# pcb.net
KiCad netlist of a schematic drawn in Altium Designer
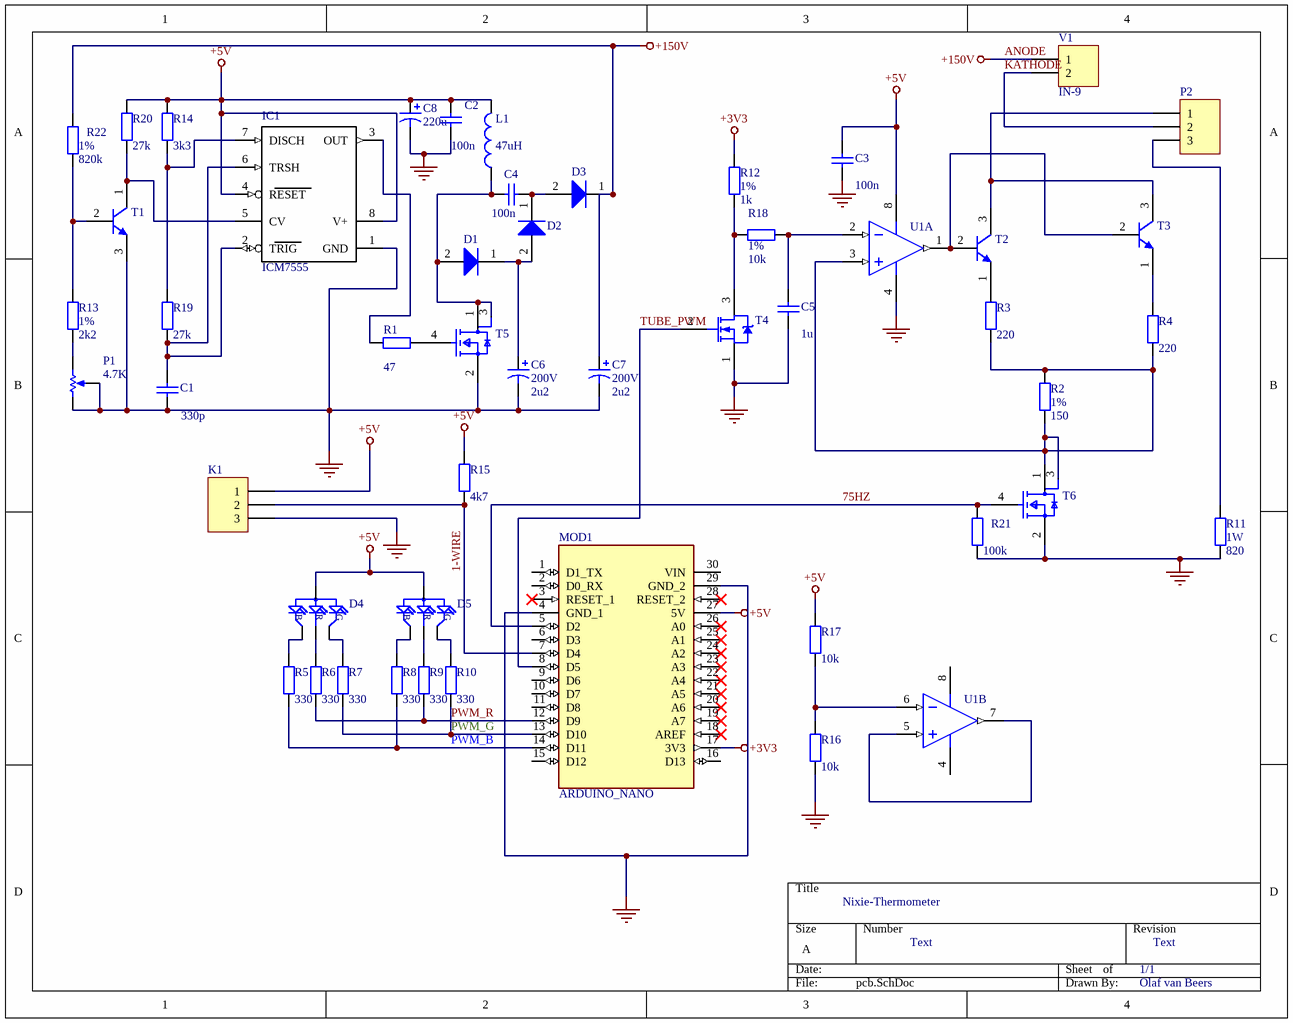
[diagram p0: pcb.SchDoc]

(export (version "E")
  (design (tool "Eeschema 10.0.6"))
  (components
    (comp (ref "C1")
      (value "330p")
      (footprint "RAD-0.3")
      (description "Capacitor")
      (fields (field (name "Comment") "Cap") (field (name "PUBLISHER") "Altium Limited"))
      (libsource (lib "Miscellaneous Devices") (part "Cap"))
    )
    (comp (ref "C2")
      (value "100n")
      (footprint "RAD-0.3")
      (description "Capacitor")
      (fields (field (name "Comment") "Cap") (field (name "PUBLISHER") "Altium Limited"))
      (libsource (lib "Miscellaneous Devices") (part "Cap"))
    )
    (comp (ref "C3")
      (value "100n")
      (footprint "RAD-0.3")
      (description "Capacitor")
      (fields (field (name "Comment") "Cap") (field (name "PUBLISHER") "Altium Limited"))
      (libsource (lib "Miscellaneous Devices") (part "Cap"))
    )
    (comp (ref "C4")
      (value "100n")
      (footprint "RAD-0.3")
      (description "Capacitor")
      (fields (field (name "Comment") "Cap") (field (name "PUBLISHER") "Altium Limited"))
      (libsource (lib "Miscellaneous Devices") (part "Cap"))
    )
    (comp (ref "C5")
      (value "1u")
      (footprint "RAD-0.3")
      (description "Capacitor")
      (fields (field (name "Comment") "Cap") (field (name "PUBLISHER") "Altium Limited"))
      (libsource (lib "Miscellaneous Devices") (part "Cap"))
    )
    (comp (ref "C6")
      (value "200V")
      (footprint "Miscellaneous Devices:RB7.6-15")
      (description "Polarized Capacitor (Radial)")
      (fields (field (name "ALTIUM_VALUE") "2u2") (field (name "PUBLISHER") "Altium Limited"))
      (libsource (lib "Miscellaneous Devices") (part "Cap Pol1"))
    )
    (comp (ref "C7")
      (value "200V")
      (footprint "RB7.6-15")
      (description "Polarized Capacitor (Radial)")
      (fields (field (name "ALTIUM_VALUE") "2u2") (field (name "PUBLISHER") "Altium Limited"))
      (libsource (lib "Miscellaneous Devices") (part "Cap Pol1"))
    )
    (comp (ref "C8")
      (value "220u")
      (footprint "RB7.6-15")
      (description "Polarized Capacitor (Radial)")
      (fields (field (name "Comment") "Cap Pol1") (field (name "PUBLISHER") "Altium Limited"))
      (libsource (lib "Miscellaneous Devices") (part "Cap Pol1"))
    )
    (comp (ref "D1")
      (value "MUR160G")
      (footprint "ONSC-AXIAL_LEAD-2-59-10_P")
      (description "SWITCHMODE(TM) Power Rectifier, 2-Pin Axial_Lead, Pb-Free, Bulk Bag")
      (fields (field (name "MANUFACTURER") "On Semiconductor"))
      (libsource (lib "Components - 04.03.20 - 18.02") (part "CMP-0902-00129-1"))
    )
    (comp (ref "D2")
      (value "MUR160G")
      (footprint "ONSC-AXIAL_LEAD-2-59-10_P")
      (description "SWITCHMODE(TM) Power Rectifier, 2-Pin Axial_Lead, Pb-Free, Bulk Bag")
      (fields (field (name "MANUFACTURER") "On Semiconductor"))
      (libsource (lib "Components - 04.03.20 - 18.02") (part "CMP-0902-00129-1"))
    )
    (comp (ref "D3")
      (value "MUR160G")
      (footprint "ONSC-AXIAL_LEAD-2-59-10_P")
      (description "SWITCHMODE(TM) Power Rectifier, 2-Pin Axial_Lead, Pb-Free, Bulk Bag")
      (fields (field (name "MANUFACTURER") "On Semiconductor"))
      (libsource (lib "Components - 04.03.20 - 18.02") (part "CMP-0902-00129-1"))
    )
    (comp (ref "D4")
      (value "DIP-LED-RGB-COMMON-ANODE(4P-D8MM)")
      (footprint "*LED4-2.0-D8.0MM")
      (description "DIP LED RGB Common Anode")
      (fields (field (name "MF") "Chengguangxing") (field (name "MP") "CZXR-80RGB03-A"))
      (libsource (lib "DIP-LED-RGB-COMMON-ANODE_4P-D8MM_") (part "DIP-LED-RGB-COMMON-ANODE(4P-D8MM)"))
    )
    (comp (ref "D5")
      (value "DIP-LED-RGB-COMMON-ANODE(4P-D8MM)")
      (footprint "*LED4-2.0-D8.0MM")
      (description "DIP LED RGB Common Anode")
      (fields (field (name "MF") "Chengguangxing") (field (name "MP") "CZXR-80RGB03-A"))
      (libsource (lib "DIP-LED-RGB-COMMON-ANODE_4P-D8MM_") (part "DIP-LED-RGB-COMMON-ANODE(4P-D8MM)"))
    )
    (comp (ref "IC1") (value "ICM7555") (footprint "*DIL08") (libsource (lib "ICM7555") (part "ICM7555")))
    (comp (ref "K1")
      (value "Header 3")
      (footprint "HDR1X3")
      (description "Header, 3-Pin")
      (fields (field (name "PUBLISHER") "Altium Limited"))
      (libsource (lib "Miscellaneous Connectors") (part "Header 3"))
    )
    (comp (ref "L1")
      (value "47uH")
      (footprint "INDC3216")
      (description "Inductor")
      (fields (field (name "PUBLISHER") "Altium Limited"))
      (libsource (lib "Miscellaneous Devices") (part "Inductor"))
    )
    (comp (ref "MOD1")
      (value "ARDUINO_NANO")
      (footprint "ARDUINO_A000005")
      (description "ATmega328 Arduino Nano AVRÂ® ATmega AVR MCU 8-Bit Embedded Evaluation Board")
      (fields (field (name "MP") "A000005") (field (name "DIGI-KEY_PART_NUMBER") "1050-1001-ND"))
      (libsource (lib "A000005") (part "A000005"))
    )
    (comp (ref "P1")
      (value "4.7K")
      (footprint "VR4")
      (description "Potentiometer")
      (fields (field (name "Comment") "RPot") (field (name "PUBLISHER") "Altium Limited"))
      (libsource (lib "Miscellaneous Devices") (part "RPot"))
    )
    (comp (ref "P2")
      (value "Header 3")
      (footprint "HDR1X3")
      (description "Header, 3-Pin")
      (fields (field (name "PUBLISHER") "Altium Limited"))
      (libsource (lib "") (part "Header 3_1"))
    )
    (comp (ref "R1")
      (value "47")
      (footprint "Miscellaneous Devices:AXIAL-0.4")
      (description "Resistor")
      (fields (field (name "Comment") "Res2") (field (name "PUBLISHER") "Altium Limited"))
      (libsource (lib "") (part "Res2_2"))
    )
    (comp (ref "R2")
      (value "1%")
      (footprint "AXIAL-0.4")
      (description "Resistor")
      (fields (field (name "ALTIUM_VALUE") "150") (field (name "PUBLISHER") "Altium Limited"))
      (libsource (lib "") (part "Res2_1"))
    )
    (comp (ref "R3")
      (value "220")
      (footprint "Miscellaneous Devices:AXIAL-0.4")
      (description "Resistor")
      (fields (field (name "Comment") "Res2") (field (name "PUBLISHER") "Altium Limited"))
      (libsource (lib "") (part "Res2_1"))
    )
    (comp (ref "R4")
      (value "220")
      (footprint "Miscellaneous Devices:AXIAL-0.4")
      (description "Resistor")
      (fields (field (name "Comment") "Res2") (field (name "PUBLISHER") "Altium Limited"))
      (libsource (lib "") (part "Res2_1"))
    )
    (comp (ref "R5")
      (value "330")
      (footprint "Miscellaneous Devices:AXIAL-0.4")
      (description "Resistor")
      (fields (field (name "Comment") "Res2") (field (name "PUBLISHER") "Altium Limited"))
      (libsource (lib "") (part "Res2_1"))
    )
    (comp (ref "R6")
      (value "330")
      (footprint "Miscellaneous Devices:AXIAL-0.4")
      (description "Resistor")
      (fields (field (name "Comment") "Res2") (field (name "PUBLISHER") "Altium Limited"))
      (libsource (lib "") (part "Res2_1"))
    )
    (comp (ref "R7")
      (value "330")
      (footprint "Miscellaneous Devices:AXIAL-0.4")
      (description "Resistor")
      (fields (field (name "Comment") "Res2") (field (name "PUBLISHER") "Altium Limited"))
      (libsource (lib "") (part "Res2_1"))
    )
    (comp (ref "R8")
      (value "330")
      (footprint "Miscellaneous Devices:AXIAL-0.4")
      (description "Resistor")
      (fields (field (name "Comment") "Res2") (field (name "PUBLISHER") "Altium Limited"))
      (libsource (lib "") (part "Res2_1"))
    )
    (comp (ref "R9")
      (value "330")
      (footprint "Miscellaneous Devices:AXIAL-0.4")
      (description "Resistor")
      (fields (field (name "Comment") "Res2") (field (name "PUBLISHER") "Altium Limited"))
      (libsource (lib "") (part "Res2_1"))
    )
    (comp (ref "R10")
      (value "330")
      (footprint "Miscellaneous Devices:AXIAL-0.4")
      (description "Resistor")
      (fields (field (name "Comment") "Res2") (field (name "PUBLISHER") "Altium Limited"))
      (libsource (lib "") (part "Res2_1"))
    )
    (comp (ref "R11")
      (value "1W")
      (footprint "AXIAL-0.4")
      (description "Resistor")
      (fields (field (name "ALTIUM_VALUE") "820") (field (name "PUBLISHER") "Altium Limited"))
      (libsource (lib "Miscellaneous Devices") (part "Res2"))
    )
    (comp (ref "R12")
      (value "1%")
      (footprint "AXIAL-0.4")
      (description "Resistor")
      (fields (field (name "ALTIUM_VALUE") "1k") (field (name "PUBLISHER") "Altium Limited"))
      (libsource (lib "") (part "Res2_1"))
    )
    (comp (ref "R13")
      (value "1%")
      (footprint "AXIAL-0.4")
      (description "Resistor")
      (fields (field (name "ALTIUM_VALUE") "2k2") (field (name "PUBLISHER") "Altium Limited"))
      (libsource (lib "") (part "Res2_1"))
    )
    (comp (ref "R14")
      (value "3k3")
      (footprint "Miscellaneous Devices:AXIAL-0.4")
      (description "Resistor")
      (fields (field (name "Comment") "Res2") (field (name "PUBLISHER") "Altium Limited"))
      (libsource (lib "") (part "Res2_1"))
    )
    (comp (ref "R15")
      (value "4k7")
      (footprint "Miscellaneous Devices:AXIAL-0.4")
      (description "Resistor")
      (fields (field (name "Comment") "Res2") (field (name "PUBLISHER") "Altium Limited"))
      (libsource (lib "") (part "Res2_1"))
    )
    (comp (ref "R16")
      (value "10k")
      (footprint "Miscellaneous Devices:AXIAL-0.4")
      (description "Resistor")
      (fields (field (name "Comment") "Res2") (field (name "PUBLISHER") "Altium Limited"))
      (libsource (lib "") (part "Res2_1"))
    )
    (comp (ref "R17")
      (value "10k")
      (footprint "Miscellaneous Devices:AXIAL-0.4")
      (description "Resistor")
      (fields (field (name "Comment") "Res2") (field (name "PUBLISHER") "Altium Limited"))
      (libsource (lib "") (part "Res2_1"))
    )
    (comp (ref "R18")
      (value "1%")
      (footprint "AXIAL-0.4")
      (description "Resistor")
      (fields (field (name "ALTIUM_VALUE") "10k") (field (name "PUBLISHER") "Altium Limited"))
      (libsource (lib "") (part "Res2_2"))
    )
    (comp (ref "R19")
      (value "27k")
      (footprint "Miscellaneous Devices:AXIAL-0.4")
      (description "Resistor")
      (fields (field (name "Comment") "Res2") (field (name "PUBLISHER") "Altium Limited"))
      (libsource (lib "") (part "Res2_1"))
    )
    (comp (ref "R20")
      (value "27k")
      (footprint "Miscellaneous Devices:AXIAL-0.4")
      (description "Resistor")
      (fields (field (name "Comment") "Res2") (field (name "PUBLISHER") "Altium Limited"))
      (libsource (lib "") (part "Res2_1"))
    )
    (comp (ref "R21")
      (value "100k")
      (footprint "Miscellaneous Devices:AXIAL-0.4")
      (description "Resistor")
      (fields (field (name "Comment") "Res2") (field (name "PUBLISHER") "Altium Limited"))
      (libsource (lib "") (part "Res2_1"))
    )
    (comp (ref "R22")
      (value "1%")
      (footprint "AXIAL-0.4")
      (description "Resistor")
      (fields (field (name "ALTIUM_VALUE") "820k") (field (name "PUBLISHER") "Altium Limited"))
      (libsource (lib "") (part "Res2_1"))
    )
    (comp (ref "T1")
      (value "BC547B")
      (footprint "ONSC-TO-92-3-29-11")
      (description "Amplifier Transistor, NPN Silicon, 3-Pin TO-92, Bulk Box")
      (fields (field (name "MANUFACTURER") "On Semiconductor"))
      (libsource (lib "Components - 04.03.20 - 18.02") (part "CMP-1048-01467-1"))
    )
    (comp (ref "T2")
      (value "MPSA42")
      (footprint "ONSC-TO-92-3-29-11")
      (description "High Voltage Transistor, NPN Silicon, 3-Pin TO-92, Bulk Box")
      (fields (field (name "MANUFACTURER") "On Semiconductor"))
      (libsource (lib "Components - 04.03.20 - 18.02") (part "CMP-1048-01390-1"))
    )
    (comp (ref "T3")
      (value "MPSA42")
      (footprint "ONSC-TO-92-3-29-11")
      (description "High Voltage Transistor, NPN Silicon, 3-Pin TO-92, Bulk Box")
      (fields (field (name "MANUFACTURER") "On Semiconductor"))
      (libsource (lib "Components - 04.03.20 - 18.02") (part "CMP-1048-01390-1"))
    )
    (comp (ref "T4")
      (value "2N7000")
      (footprint "ONSC-TO-92-3-29-11")
      (description "Small Signal MOSFET, 200 mA, 60 V, N-Channel, 3-Pin TO-92, Bulk Box")
      (fields (field (name "MANUFACTURER") "On Semiconductor"))
      (libsource (lib "Components - 04.03.20 - 18.02") (part "CMP-1058-00936-1"))
    )
    (comp (ref "T5")
      (value "IRFD110PBF")
      (footprint "Vishay_X10-0386_MFG")
      (libsource (lib "Trans_Vishay_IRFD110PBF_eec") (part "IRFD110PBF"))
    )
    (comp (ref "T6")
      (value "IRFD110PBF")
      (footprint "Vishay_X10-0386_MFG")
      (libsource (lib "Trans_Vishay_IRFD110PBF_eec") (part "IRFD110PBF"))
    )
    (comp (ref "U1")
      (value "LM6142AIM")
      (footprint "D0008A_N")
      (description "Dual High Speed/Low Power 17 MHz Rail-to-Rail I/O Operational Amplifier, 8-pin Narrow SOIC")
      (fields (field (name "MANUFACTURER") "Texas Instruments"))
      (libsource (lib "Altium Content Vault") (part "AMP-OPA-LM6132-8"))
    )
    (comp (ref "V1")
      (value "IN-9")
      (footprint "HDR1X2")
      (description "Header, 2-Pin")
      (fields (field (name "PUBLISHER") "Altium Limited"))
      (libsource (lib "Miscellaneous Connectors") (part "Header 2"))
    )
  )
  (nets
    (net (code "1") (name "+3V3") (class "Default")
      (node (ref "MOD1") (pin "17") (pinfunction "3V3_17") (pintype "output"))
      (node (ref "R12") (pin "2") (pinfunction "2_2") (pintype "passive"))
    )
    (net (code "2") (name "+5V") (class "Default")
      (node (ref "C2") (pin "2") (pinfunction "2_2") (pintype "passive"))
      (node (ref "C3") (pin "2") (pinfunction "2_2") (pintype "passive"))
      (node (ref "C8") (pin "1") (pinfunction "1_1") (pintype "passive"))
      (node (ref "D4") (pin "2") (pinfunction "POS_2") (pintype "bidirectional"))
      (node (ref "D5") (pin "2") (pinfunction "POS_2") (pintype "bidirectional"))
      (node (ref "IC1") (pin "4") (pinfunction "RESET_4") (pintype "input"))
      (node (ref "IC1") (pin "8") (pinfunction "V+_8") (pintype "power_in"))
      (node (ref "K1") (pin "1") (pinfunction "1_1") (pintype "passive"))
      (node (ref "L1") (pin "2") (pinfunction "2_2") (pintype "passive"))
      (node (ref "MOD1") (pin "27") (pinfunction "5V_27") (pintype "power_in"))
      (node (ref "R14") (pin "2") (pinfunction "2_2") (pintype "passive"))
      (node (ref "R15") (pin "2") (pinfunction "2_2") (pintype "passive"))
      (node (ref "R17") (pin "2") (pinfunction "2_2") (pintype "passive"))
      (node (ref "R20") (pin "2") (pinfunction "2_2") (pintype "passive"))
      (node (ref "U1") (pin "8") (pinfunction "V+_8") (pintype "power_in"))
    )
    (net (code "3") (name "+150V") (class "Default")
      (node (ref "C7") (pin "1") (pinfunction "1_1") (pintype "passive"))
      (node (ref "D3") (pin "1") (pinfunction "K_1") (pintype "passive"))
      (node (ref "R22") (pin "2") (pinfunction "2_2") (pintype "passive"))
      (node (ref "V1") (pin "1") (pinfunction "1_1") (pintype "passive"))
    )
    (net (code "4") (name "/1-WIRE") (class "Default")
      (node (ref "K1") (pin "2") (pinfunction "2_2") (pintype "passive"))
      (node (ref "MOD1") (pin "7") (pinfunction "D4_7") (pintype "bidirectional"))
      (node (ref "R15") (pin "1") (pinfunction "1_1") (pintype "passive"))
    )
    (net (code "5") (name "/75HZ") (class "Default")
      (node (ref "MOD1") (pin "5") (pinfunction "D2_5") (pintype "bidirectional"))
      (node (ref "R21") (pin "2") (pinfunction "2_2") (pintype "passive"))
      (node (ref "T6") (pin "4") (pinfunction "G_4") (pintype "passive"))
    )
    (net (code "6") (name "/KATHODE") (class "Default")
      (node (ref "P2") (pin "2") (pinfunction "2_2") (pintype "passive"))
      (node (ref "V1") (pin "2") (pinfunction "2_2") (pintype "passive"))
    )
    (net (code "7") (name "/PWM_B") (class "Default")
      (node (ref "MOD1") (pin "14") (pinfunction "D11_14") (pintype "bidirectional"))
      (node (ref "R5") (pin "1") (pinfunction "1_1") (pintype "passive"))
      (node (ref "R8") (pin "1") (pinfunction "1_1") (pintype "passive"))
    )
    (net (code "8") (name "/PWM_G") (class "Default")
      (node (ref "MOD1") (pin "12") (pinfunction "D9_12") (pintype "bidirectional"))
      (node (ref "MOD1") (pin "13") (pinfunction "D10_13") (pintype "bidirectional"))
      (node (ref "R10") (pin "1") (pinfunction "1_1") (pintype "passive"))
      (node (ref "R6") (pin "1") (pinfunction "1_1") (pintype "passive"))
      (node (ref "R7") (pin "1") (pinfunction "1_1") (pintype "passive"))
      (node (ref "R9") (pin "1") (pinfunction "1_1") (pintype "passive"))
    )
    (net (code "9") (name "/TUBE_PWM") (class "Default")
      (node (ref "MOD1") (pin "8") (pinfunction "D5_8") (pintype "bidirectional"))
      (node (ref "T4") (pin "2") (pinfunction "G_2") (pintype "passive"))
    )
    (net (code "10") (name "GND") (class "Default")
      (node (ref "C1") (pin "1") (pinfunction "1_1") (pintype "passive"))
      (node (ref "C2") (pin "1") (pinfunction "1_1") (pintype "passive"))
      (node (ref "C3") (pin "1") (pinfunction "1_1") (pintype "passive"))
      (node (ref "C5") (pin "1") (pinfunction "1_1") (pintype "passive"))
      (node (ref "C6") (pin "2") (pinfunction "2_2") (pintype "passive"))
      (node (ref "C7") (pin "2") (pinfunction "2_2") (pintype "passive"))
      (node (ref "C8") (pin "2") (pinfunction "2_2") (pintype "passive"))
      (node (ref "IC1") (pin "1") (pinfunction "GND_1") (pintype "power_in"))
      (node (ref "K1") (pin "3") (pinfunction "3_3") (pintype "passive"))
      (node (ref "MOD1") (pin "29") (pinfunction "GND_2_29") (pintype "power_in"))
      (node (ref "MOD1") (pin "4") (pinfunction "GND_1_4") (pintype "power_in"))
      (node (ref "P1") (pin "1") (pinfunction "TOP_1") (pintype "passive"))
      (node (ref "P1") (pin "3") (pinfunction "TAP_3") (pintype "passive"))
      (node (ref "R11") (pin "2") (pinfunction "2_2") (pintype "passive"))
      (node (ref "R16") (pin "1") (pinfunction "1_1") (pintype "passive"))
      (node (ref "R21") (pin "1") (pinfunction "1_1") (pintype "passive"))
      (node (ref "T1") (pin "3") (pinfunction "E_3") (pintype "passive"))
      (node (ref "T4") (pin "1") (pinfunction "S_1") (pintype "passive"))
      (node (ref "T5") (pin "2") (pinfunction "S_2") (pintype "passive"))
      (node (ref "T6") (pin "2") (pinfunction "S_2") (pintype "passive"))
      (node (ref "U1") (pin "4") (pinfunction "V-_4") (pintype "power_in"))
    )
    (net (code "11") (name "Net-(D1-A)") (class "Default")
      (node (ref "C4") (pin "1") (pinfunction "1_1") (pintype "passive"))
      (node (ref "D1") (pin "2") (pinfunction "A_2") (pintype "passive"))
      (node (ref "L1") (pin "1") (pinfunction "1_1") (pintype "passive"))
      (node (ref "T5") (pin "1") (pinfunction "D_1") (pintype "passive"))
      (node (ref "T5") (pin "3") (pinfunction "D_3") (pintype "passive"))
    )
    (net (code "12") (name "Net-(D1-K)") (class "Default")
      (node (ref "C6") (pin "1") (pinfunction "1_1") (pintype "passive"))
      (node (ref "D1") (pin "1") (pinfunction "K_1") (pintype "passive"))
      (node (ref "D2") (pin "2") (pinfunction "A_2") (pintype "passive"))
    )
    (net (code "13") (name "Net-(D2-K)") (class "Default")
      (node (ref "C4") (pin "2") (pinfunction "2_2") (pintype "passive"))
      (node (ref "D2") (pin "1") (pinfunction "K_1") (pintype "passive"))
      (node (ref "D3") (pin "2") (pinfunction "A_2") (pintype "passive"))
    )
    (net (code "14") (name "Net-(D4-B)") (class "Default")
      (node (ref "D4") (pin "4") (pinfunction "B_4") (pintype "bidirectional"))
      (node (ref "R5") (pin "2") (pinfunction "2_2") (pintype "passive"))
    )
    (net (code "15") (name "Net-(D4-G)") (class "Default")
      (node (ref "D4") (pin "3") (pinfunction "G_3") (pintype "bidirectional"))
      (node (ref "R7") (pin "2") (pinfunction "2_2") (pintype "passive"))
    )
    (net (code "16") (name "Net-(D4-R)") (class "Default")
      (node (ref "D4") (pin "1") (pinfunction "R_1") (pintype "bidirectional"))
      (node (ref "R6") (pin "2") (pinfunction "2_2") (pintype "passive"))
    )
    (net (code "17") (name "Net-(D5-B)") (class "Default")
      (node (ref "D5") (pin "4") (pinfunction "B_4") (pintype "bidirectional"))
      (node (ref "R8") (pin "2") (pinfunction "2_2") (pintype "passive"))
    )
    (net (code "18") (name "Net-(D5-G)") (class "Default")
      (node (ref "D5") (pin "3") (pinfunction "G_3") (pintype "bidirectional"))
      (node (ref "R10") (pin "2") (pinfunction "2_2") (pintype "passive"))
    )
    (net (code "19") (name "Net-(D5-R)") (class "Default")
      (node (ref "D5") (pin "1") (pinfunction "R_1") (pintype "bidirectional"))
      (node (ref "R9") (pin "2") (pinfunction "2_2") (pintype "passive"))
    )
    (net (code "20") (name "Net-(IC1-CV)") (class "Default")
      (node (ref "IC1") (pin "5") (pinfunction "CV_5") (pintype "passive"))
      (node (ref "R20") (pin "1") (pinfunction "1_1") (pintype "passive"))
      (node (ref "T1") (pin "1") (pinfunction "C_1") (pintype "passive"))
    )
    (net (code "21") (name "Net-(IC1-DISCH)") (class "Default")
      (node (ref "IC1") (pin "7") (pinfunction "DISCH_7") (pintype "input"))
      (node (ref "R14") (pin "1") (pinfunction "1_1") (pintype "passive"))
      (node (ref "R19") (pin "2") (pinfunction "2_2") (pintype "passive"))
    )
    (net (code "22") (name "Net-(IC1-OUT)") (class "Default")
      (node (ref "IC1") (pin "3") (pinfunction "OUT_3") (pintype "output"))
      (node (ref "R1") (pin "1") (pinfunction "1_1") (pintype "passive"))
    )
    (net (code "23") (name "Net-(IC1-TRIG)") (class "Default")
      (node (ref "C1") (pin "2") (pinfunction "2_2") (pintype "passive"))
      (node (ref "IC1") (pin "2") (pinfunction "TRIG_2") (pintype "bidirectional"))
      (node (ref "IC1") (pin "6") (pinfunction "TRSH_6") (pintype "input"))
      (node (ref "R19") (pin "1") (pinfunction "1_1") (pintype "passive"))
    )
    (net (code "24") (name "Net-(P1-BOT)") (class "Default")
      (node (ref "P1") (pin "2") (pinfunction "BOT_2") (pintype "passive"))
      (node (ref "R13") (pin "1") (pinfunction "1_1") (pintype "passive"))
    )
    (net (code "25") (name "Net-(P2-Pad3)") (class "Default")
      (node (ref "P2") (pin "3") (pinfunction "3_3") (pintype "passive"))
      (node (ref "R11") (pin "1") (pinfunction "1_1") (pintype "passive"))
    )
    (net (code "26") (name "Net-(T1-B)") (class "Default")
      (node (ref "R13") (pin "2") (pinfunction "2_2") (pintype "passive"))
      (node (ref "R22") (pin "1") (pinfunction "1_1") (pintype "passive"))
      (node (ref "T1") (pin "2") (pinfunction "B_2") (pintype "passive"))
    )
    (net (code "27") (name "Net-(T2-B)") (class "Default")
      (node (ref "T2") (pin "2") (pinfunction "B_2") (pintype "passive"))
      (node (ref "T3") (pin "2") (pinfunction "B_2") (pintype "passive"))
      (node (ref "U1") (pin "1") (pinfunction "OUTA_1") (pintype "output"))
    )
    (net (code "28") (name "Net-(T2-C)") (class "Default")
      (node (ref "P2") (pin "1") (pinfunction "1_1") (pintype "passive"))
      (node (ref "T2") (pin "3") (pinfunction "C_3") (pintype "passive"))
      (node (ref "T3") (pin "3") (pinfunction "C_3") (pintype "passive"))
    )
    (net (code "29") (name "Net-(T2-E)") (class "Default")
      (node (ref "R3") (pin "2") (pinfunction "2_2") (pintype "passive"))
      (node (ref "T2") (pin "1") (pinfunction "E_1") (pintype "passive"))
    )
    (net (code "30") (name "Net-(T3-E)") (class "Default")
      (node (ref "R4") (pin "2") (pinfunction "2_2") (pintype "passive"))
      (node (ref "T3") (pin "1") (pinfunction "E_1") (pintype "passive"))
    )
    (net (code "31") (name "Net-(T4-D)") (class "Default")
      (node (ref "R12") (pin "1") (pinfunction "1_1") (pintype "passive"))
      (node (ref "R18") (pin "1") (pinfunction "1_1") (pintype "passive"))
      (node (ref "T4") (pin "3") (pinfunction "D_3") (pintype "passive"))
    )
    (net (code "32") (name "Net-(T5-G)") (class "Default")
      (node (ref "R1") (pin "2") (pinfunction "2_2") (pintype "passive"))
      (node (ref "T5") (pin "4") (pinfunction "G_4") (pintype "passive"))
    )
    (net (code "33") (name "Net-(U1A-INA+)") (class "Default")
      (node (ref "R2") (pin "1") (pinfunction "1_1") (pintype "passive"))
      (node (ref "R2") (pin "2") (pinfunction "2_2") (pintype "passive"))
      (node (ref "R3") (pin "1") (pinfunction "1_1") (pintype "passive"))
      (node (ref "R4") (pin "1") (pinfunction "1_1") (pintype "passive"))
      (node (ref "T6") (pin "1") (pinfunction "D_1") (pintype "passive"))
      (node (ref "T6") (pin "3") (pinfunction "D_3") (pintype "passive"))
      (node (ref "U1") (pin "3") (pinfunction "INA+_3") (pintype "input"))
    )
    (net (code "34") (name "Net-(U1A-INA-)") (class "Default")
      (node (ref "C5") (pin "2") (pinfunction "2_2") (pintype "passive"))
      (node (ref "R18") (pin "2") (pinfunction "2_2") (pintype "passive"))
      (node (ref "U1") (pin "2") (pinfunction "INA-_2") (pintype "input"))
    )
    (net (code "35") (name "Net-(U1B-INB+)") (class "Default")
      (node (ref "U1") (pin "5") (pinfunction "INB+_5") (pintype "input"))
      (node (ref "U1") (pin "7") (pinfunction "OUTB_7") (pintype "output"))
    )
    (net (code "36") (name "Net-(U1B-INB-)") (class "Default")
      (node (ref "R16") (pin "2") (pinfunction "2_2") (pintype "passive"))
      (node (ref "R17") (pin "1") (pinfunction "1_1") (pintype "passive"))
      (node (ref "U1") (pin "6") (pinfunction "INB-_6") (pintype "input"))
    )
    (net (code "37") (name "unconnected-(MOD1-A0-Pad26)") (class "Default")
      (node (ref "MOD1") (pin "26") (pinfunction "A0_26") (pintype "input+no_connect"))
    )
    (net (code "38") (name "unconnected-(MOD1-A1-Pad25)") (class "Default")
      (node (ref "MOD1") (pin "25") (pinfunction "A1_25") (pintype "input+no_connect"))
    )
    (net (code "39") (name "unconnected-(MOD1-A2-Pad24)") (class "Default")
      (node (ref "MOD1") (pin "24") (pinfunction "A2_24") (pintype "input+no_connect"))
    )
    (net (code "40") (name "unconnected-(MOD1-A3-Pad23)") (class "Default")
      (node (ref "MOD1") (pin "23") (pinfunction "A3_23") (pintype "input+no_connect"))
    )
    (net (code "41") (name "unconnected-(MOD1-A4-Pad22)") (class "Default")
      (node (ref "MOD1") (pin "22") (pinfunction "A4_22") (pintype "input+no_connect"))
    )
    (net (code "42") (name "unconnected-(MOD1-A5-Pad21)") (class "Default")
      (node (ref "MOD1") (pin "21") (pinfunction "A5_21") (pintype "input+no_connect"))
    )
    (net (code "43") (name "unconnected-(MOD1-A6-Pad20)") (class "Default")
      (node (ref "MOD1") (pin "20") (pinfunction "A6_20") (pintype "input+no_connect"))
    )
    (net (code "44") (name "unconnected-(MOD1-A7-Pad19)") (class "Default")
      (node (ref "MOD1") (pin "19") (pinfunction "A7_19") (pintype "input+no_connect"))
    )
    (net (code "45") (name "unconnected-(MOD1-AREF-Pad18)") (class "Default")
      (node (ref "MOD1") (pin "18") (pinfunction "AREF_18") (pintype "input+no_connect"))
    )
    (net (code "46") (name "unconnected-(MOD1-D0_RX-Pad2)") (class "Default")
      (node (ref "MOD1") (pin "2") (pinfunction "D0_RX_2") (pintype "bidirectional"))
    )
    (net (code "47") (name "unconnected-(MOD1-D1_TX-Pad1)") (class "Default")
      (node (ref "MOD1") (pin "1") (pinfunction "D1_TX_1") (pintype "bidirectional"))
    )
    (net (code "48") (name "unconnected-(MOD1-D3-Pad6)") (class "Default")
      (node (ref "MOD1") (pin "6") (pinfunction "D3_6") (pintype "bidirectional"))
    )
    (net (code "49") (name "unconnected-(MOD1-D6-Pad9)") (class "Default")
      (node (ref "MOD1") (pin "9") (pinfunction "D6_9") (pintype "bidirectional"))
    )
    (net (code "50") (name "unconnected-(MOD1-D7-Pad10)") (class "Default")
      (node (ref "MOD1") (pin "10") (pinfunction "D7_10") (pintype "bidirectional"))
    )
    (net (code "51") (name "unconnected-(MOD1-D8-Pad11)") (class "Default")
      (node (ref "MOD1") (pin "11") (pinfunction "D8_11") (pintype "bidirectional"))
    )
    (net (code "52") (name "unconnected-(MOD1-D12-Pad15)") (class "Default")
      (node (ref "MOD1") (pin "15") (pinfunction "D12_15") (pintype "bidirectional"))
    )
    (net (code "53") (name "unconnected-(MOD1-D13-Pad16)") (class "Default")
      (node (ref "MOD1") (pin "16") (pinfunction "D13_16") (pintype "bidirectional"))
    )
    (net (code "54") (name "unconnected-(MOD1-RESET_1-Pad3)") (class "Default")
      (node (ref "MOD1") (pin "3") (pinfunction "RESET_1_3") (pintype "input+no_connect"))
    )
    (net (code "55") (name "unconnected-(MOD1-RESET_2-Pad28)") (class "Default")
      (node (ref "MOD1") (pin "28") (pinfunction "RESET_2_28") (pintype "input+no_connect"))
    )
    (net (code "56") (name "unconnected-(MOD1-VIN-Pad30)") (class "Default")
      (node (ref "MOD1") (pin "30") (pinfunction "VIN_30") (pintype "power_in"))
    )
    (net (code "57") (name "unconnected-(U1B-V+-Pad8)") (class "Default")
      (node (ref "U1") (pin "8") (pinfunction "V+_8") (pintype "power_in"))
    )
    (net (code "58") (name "unconnected-(U1B-V--Pad4)") (class "Default")
      (node (ref "U1") (pin "4") (pinfunction "V-_4") (pintype "power_in"))
    )
  )
)
